# buzzerWithBattery.net
KiCad netlist of a schematic drawn in Altium Designer
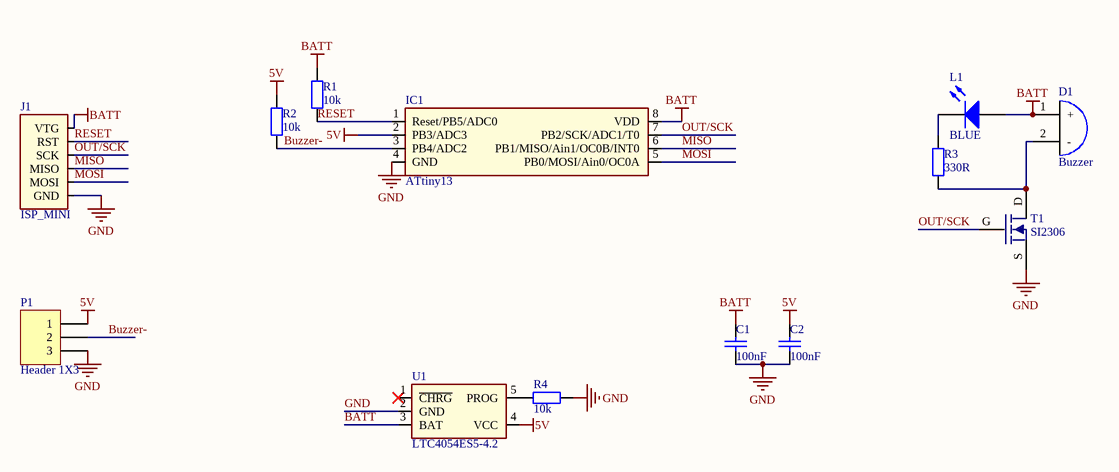
[diagram p0: buzzerWithBattery.SchDoc]

(export (version "E")
  (design (tool "Eeschema 10.0.6"))
  (components
    (comp (ref "C1")
      (value "100nF")
      (footprint "FP_0603_CAP_080")
      (description "Capacitor")
      (fields (field (name "PART NUMBER") "100nF_0603_50V_X7R_10percent"))
      (libsource (lib "Capacitor") (part "CAP"))
    )
    (comp (ref "C2")
      (value "100nF")
      (footprint "FP_0603_CAP_080")
      (description "Capacitor")
      (fields (field (name "PART NUMBER") "100nF_0603_50V_X7R_10percent"))
      (libsource (lib "Capacitor") (part "CAP"))
    )
    (comp (ref "D1") (value "Buzzer") (footprint "Buzzer_MBS12XXX") (libsource (lib "Other") (part "Buzzer")))
    (comp (ref "IC1")
      (value "ATtiny13")
      (footprint "DIGITAL_SOIC8_WSON")
      (libsource (lib "uC") (part "ATtiny13"))
    )
    (comp (ref "J1")
      (value "ISP_MINI")
      (footprint "AVR_ISP_MINI")
      (libsource (lib "Connector") (part "ISP_MINI"))
    )
    (comp (ref "L1")
      (value "BLUE")
      (footprint "FP_0603_LED_B")
      (description "Typical LED")
      (fields (field (name "PART NUMBER") "Blue_Led_0603"))
      (libsource (lib "Led_optical") (part "LED_B"))
    )
    (comp (ref "P1")
      (value "Header 1X3")
      (footprint "HEADER_2.54MM_M_1x3")
      (description "Header, 3-Pin")
      (fields (field (name "PUBLISHER") "Altium Limited"))
      (libsource (lib "Header") (part "Header 1X3"))
    )
    (comp (ref "R1")
      (value "10k")
      (footprint "FP_0603_RES")
      (description "Resistor")
      (fields (field (name "PART NUMBER") "10k_0603_1percent"))
      (libsource (lib "Miscellaneous Devices") (part "Res3"))
    )
    (comp (ref "R2")
      (value "10k")
      (footprint "FP_0603_RES")
      (description "Resistor")
      (fields (field (name "PART NUMBER") "10k_0603_1percent"))
      (libsource (lib "Miscellaneous Devices") (part "Res3"))
    )
    (comp (ref "R3")
      (value "330R")
      (footprint "FP_0603_RES")
      (description "Resistor")
      (fields (field (name "PART NUMBER") "330R_0603_1percent"))
      (libsource (lib "Resistor") (part "RES"))
    )
    (comp (ref "R4")
      (value "10k")
      (footprint "FP_0603_RES")
      (description "Resistor")
      (fields (field (name "PART NUMBER") "10k_0603_1percent"))
      (libsource (lib "") (part "Res3_1"))
    )
    (comp (ref "T1") (value "SI2306") (footprint "FET_SOT23") (libsource (lib "FET") (part "NMOS")))
    (comp (ref "U1")
      (value "LTC4054ES5-4.2")
      (footprint "SUPPLY_SOT23-5")
      (description "LiPo charger 800mA")
      (libsource (lib "Supply") (part "LTC4054ES5-4.2"))
    )
  )
  (nets
    (net (code "1") (name "/Buzzer-") (class "Default")
      (node (ref "IC1") (pin "3") (pinfunction "PB4/ADC2_3") (pintype "passive"))
      (node (ref "P1") (pin "2") (pinfunction "2_2") (pintype "passive"))
      (node (ref "R2") (pin "1") (pinfunction "1_1") (pintype "passive"))
    )
    (net (code "2") (name "/MISO") (class "Default")
      (node (ref "IC1") (pin "6") (pinfunction "PB1/MISO/Ain1/OC0B/INT0_6") (pintype "passive"))
      (node (ref "J1") (pin "4") (pinfunction "MISO_4") (pintype "passive"))
    )
    (net (code "3") (name "/MOSI") (class "Default")
      (node (ref "IC1") (pin "5") (pinfunction "PB0/MOSI/Ain0/OC0A_5") (pintype "passive"))
      (node (ref "J1") (pin "5") (pinfunction "MOSI_5") (pintype "passive"))
    )
    (net (code "4") (name "/OUT{slash}SCK") (class "Default")
      (node (ref "IC1") (pin "7") (pinfunction "PB2/SCK/ADC1/T0_7") (pintype "passive"))
      (node (ref "J1") (pin "3") (pinfunction "SCK_3") (pintype "passive"))
      (node (ref "T1") (pin "G") (pinfunction "G_G") (pintype "passive"))
    )
    (net (code "5") (name "/RESET") (class "Default")
      (node (ref "IC1") (pin "1") (pinfunction "Reset/PB5/ADC0_1") (pintype "passive"))
      (node (ref "J1") (pin "2") (pinfunction "RST_2") (pintype "passive"))
      (node (ref "R1") (pin "1") (pinfunction "1_1") (pintype "passive"))
    )
    (net (code "6") (name "5V") (class "Default")
      (node (ref "C2") (pin "2") (pinfunction "2_2") (pintype "passive"))
      (node (ref "IC1") (pin "2") (pinfunction "PB3/ADC3_2") (pintype "passive"))
      (node (ref "P1") (pin "1") (pinfunction "1_1") (pintype "passive"))
      (node (ref "R2") (pin "2") (pinfunction "2_2") (pintype "passive"))
      (node (ref "U1") (pin "4") (pinfunction "VCC_4") (pintype "passive"))
    )
    (net (code "7") (name "BATT") (class "Default")
      (node (ref "C1") (pin "2") (pinfunction "2_2") (pintype "passive"))
      (node (ref "D1") (pin "1") (pinfunction "+_1") (pintype "passive"))
      (node (ref "IC1") (pin "8") (pinfunction "VDD_8") (pintype "passive"))
      (node (ref "J1") (pin "1") (pinfunction "VTG_1") (pintype "passive"))
      (node (ref "L1") (pin "A") (pinfunction "A_A") (pintype "passive"))
      (node (ref "R1") (pin "2") (pinfunction "2_2") (pintype "passive"))
      (node (ref "U1") (pin "3") (pinfunction "BAT_3") (pintype "passive"))
    )
    (net (code "8") (name "GND") (class "Default")
      (node (ref "C1") (pin "1") (pinfunction "1_1") (pintype "passive"))
      (node (ref "C2") (pin "1") (pinfunction "1_1") (pintype "passive"))
      (node (ref "IC1") (pin "4") (pinfunction "GND_4") (pintype "passive"))
      (node (ref "J1") (pin "6") (pinfunction "GND_6") (pintype "passive"))
      (node (ref "P1") (pin "3") (pinfunction "3_3") (pintype "passive"))
      (node (ref "R4") (pin "2") (pinfunction "2_2") (pintype "passive"))
      (node (ref "T1") (pin "S") (pinfunction "S_S") (pintype "passive"))
      (node (ref "U1") (pin "2") (pinfunction "GND_2") (pintype "passive"))
    )
    (net (code "9") (name "Net-(D1--)") (class "Default")
      (node (ref "D1") (pin "2") (pinfunction "-_2") (pintype "passive"))
      (node (ref "R3") (pin "2") (pinfunction "2_2") (pintype "passive"))
      (node (ref "T1") (pin "D") (pinfunction "D_D") (pintype "passive"))
    )
    (net (code "10") (name "Net-(L1-PadK)") (class "Default")
      (node (ref "L1") (pin "K") (pinfunction "K_K") (pintype "passive"))
      (node (ref "R3") (pin "1") (pinfunction "1_1") (pintype "passive"))
    )
    (net (code "11") (name "Net-(U1-PROG)") (class "Default")
      (node (ref "R4") (pin "1") (pinfunction "1_1") (pintype "passive"))
      (node (ref "U1") (pin "5") (pinfunction "PROG_5") (pintype "passive"))
    )
    (net (code "12") (name "unconnected-(U1-~{CHRG}-Pad1)") (class "Default")
      (node (ref "U1") (pin "1") (pinfunction "~{CHRG}_1") (pintype "passive+no_connect"))
    )
  )
)
